# STM32test.net
KiCad netlist of a schematic drawn in Altium Designer
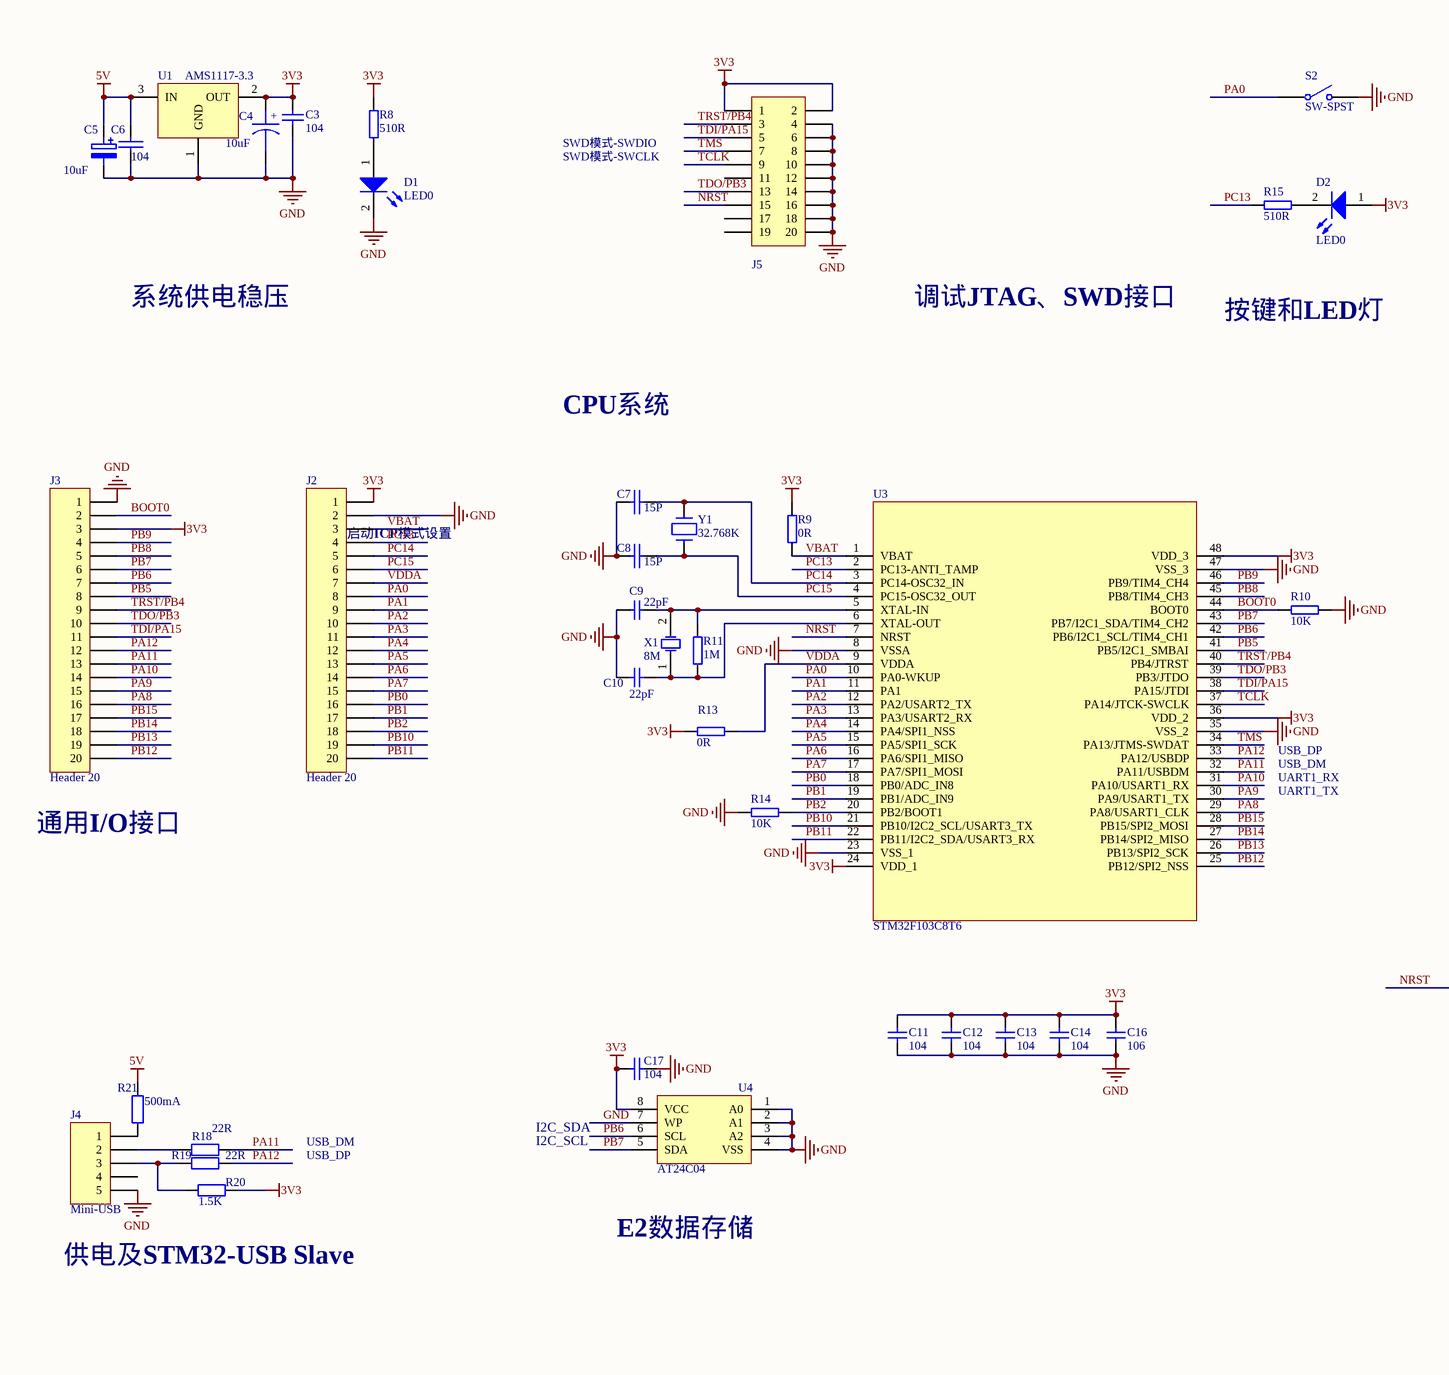
[diagram p0: STM32test.SchDoc, left]
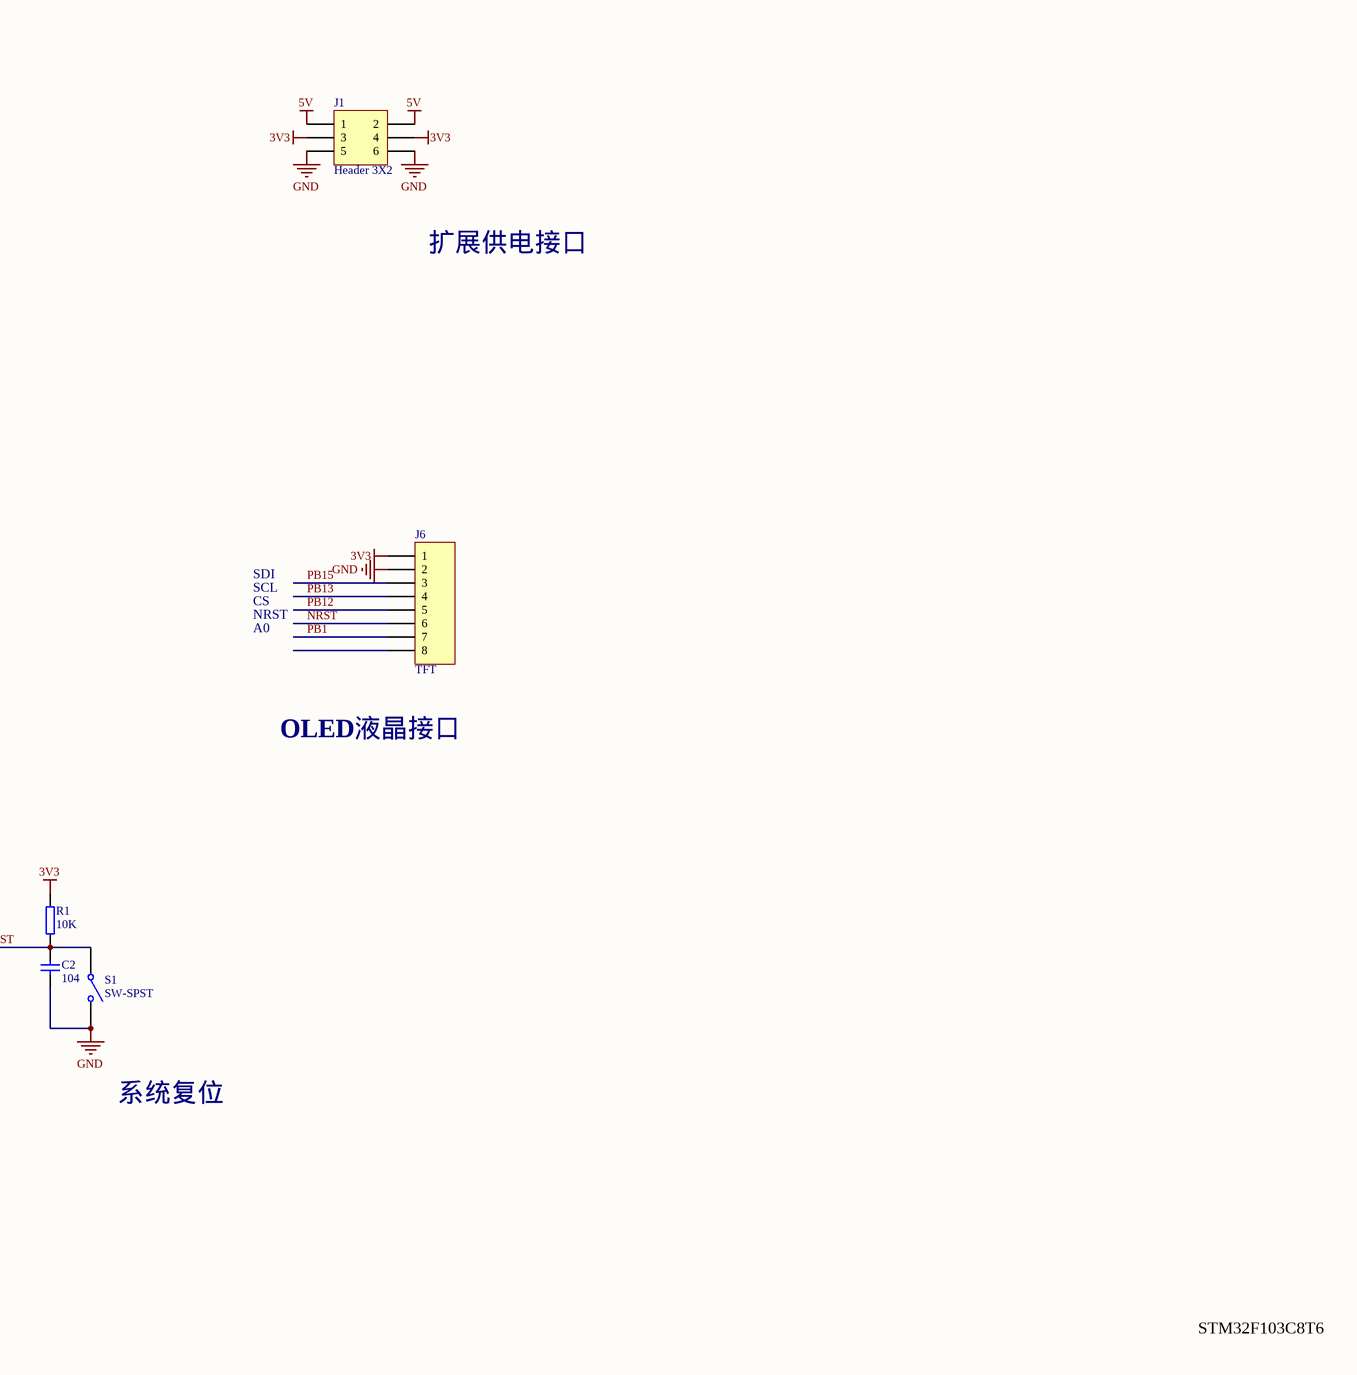
[diagram p1: STM32test.SchDoc, right]

(export (version "E")
  (design (tool "Eeschema 10.0.6"))
  (components
    (comp (ref "C2")
      (value "104")
      (footprint "RC0603")
      (description "Capacitor")
      (fields (field (name "PUBLISHER") "ZL_A0OFFICE"))
      (libsource (lib "CommomDevices") (part "CAP1"))
    )
    (comp (ref "C3")
      (value "104")
      (footprint "RC0603")
      (description "Capacitor")
      (fields (field (name "PUBLISHER") "Altium Limited"))
      (libsource (lib "*") (part "Cap"))
    )
    (comp (ref "C4")
      (value "10uF")
      (footprint "RC0805")
      (description "Capacitor")
      (libsource (lib "*") (part "CAPACITOR POL"))
    )
    (comp (ref "C5") (value "10uF") (footprint "RC0805") (libsource (lib "*") (part "ELECTRO2")))
    (comp (ref "C6")
      (value "104")
      (footprint "RC0603")
      (description "Capacitor")
      (libsource (lib "*") (part "CAP"))
    )
    (comp (ref "C7") (value "15P") (footprint "RC0603") (libsource (lib "") (part "CAP_1")))
    (comp (ref "C8") (value "15P") (footprint "RC0603") (libsource (lib "") (part "CAP_1")))
    (comp (ref "C9")
      (value "22pF")
      (footprint "RC0603")
      (description "Capacitor")
      (fields (field (name "PUBLISHER") "ZL_A0OFFICE"))
      (libsource (lib "CommomDevices") (part "CAP1"))
    )
    (comp (ref "C10")
      (value "22pF")
      (footprint "RC0603")
      (description "Capacitor")
      (fields (field (name "PUBLISHER") "ZL_A0OFFICE"))
      (libsource (lib "CommomDevices") (part "CAP1"))
    )
    (comp (ref "C11")
      (value "104")
      (footprint "RC0603")
      (description "Capacitor")
      (fields (field (name "PUBLISHER") "ZL_A0OFFICE"))
      (libsource (lib "CommomDevices") (part "CAP1"))
    )
    (comp (ref "C12")
      (value "104")
      (footprint "RC0603")
      (description "Capacitor")
      (fields (field (name "PUBLISHER") "ZL_A0OFFICE"))
      (libsource (lib "CommomDevices") (part "CAP1"))
    )
    (comp (ref "C13")
      (value "104")
      (footprint "RC0603")
      (description "Capacitor")
      (fields (field (name "PUBLISHER") "ZL_A0OFFICE"))
      (libsource (lib "CommomDevices") (part "CAP1"))
    )
    (comp (ref "C14")
      (value "104")
      (footprint "RC0603")
      (description "Capacitor")
      (fields (field (name "PUBLISHER") "ZL_A0OFFICE"))
      (libsource (lib "CommomDevices") (part "CAP1"))
    )
    (comp (ref "C16")
      (value "106")
      (footprint "RC0805")
      (description "Capacitor")
      (fields (field (name "PUBLISHER") "ZL_A0OFFICE"))
      (libsource (lib "CommomDevices") (part "CAP1"))
    )
    (comp (ref "C17")
      (value "104")
      (footprint "RC0603")
      (description "Capacitor")
      (libsource (lib "Miscellaneous Devices") (part "Cap"))
    )
    (comp (ref "D1")
      (value "LED0")
      (footprint "LED0805")
      (description "Typical INFRARED GaAs LED")
      (libsource (lib "Miscellaneous Devices") (part "LED0"))
    )
    (comp (ref "D2")
      (value "LED0")
      (footprint "LED0805")
      (description "Typical INFRARED GaAs LED")
      (libsource (lib "Miscellaneous Devices") (part "LED0"))
    )
    (comp (ref "J1")
      (value "Header 3X2")
      (footprint "IDE3X2-2.54")
      (description "Header, 3-Pin, Dual row")
      (fields (field (name "PUBLISHER") "Altium Limited"))
      (libsource (lib "Miscellaneous Connectors") (part "Header 3X2"))
    )
    (comp (ref "J2")
      (value "Header 20")
      (footprint "HDR1X20")
      (description "Header, 20-Pin")
      (fields (field (name "PUBLISHER") "Altium Limited"))
      (libsource (lib "Miscellaneous Connectors") (part "Header 20"))
    )
    (comp (ref "J3")
      (value "Header 20")
      (footprint "HDR1X20")
      (description "Header, 20-Pin")
      (fields (field (name "PUBLISHER") "Altium Limited"))
      (libsource (lib "Miscellaneous Connectors") (part "Header 20"))
    )
    (comp (ref "J4")
      (value "Mini-USB")
      (footprint "mini_USB")
      (description "Header, 5-Pin")
      (libsource (lib "Miscellaneous Connectors") (part "Header 5"))
    )
    (comp (ref "J5")
      (value "~")
      (footprint "JTAG20P")
      (description "Header, 10-Pin, Dual row, Right Angle")
      (fields (field (name "PUBLISHER") "Altium Limited"))
      (libsource (lib "Miscellaneous Connectors") (part "Header 10X2H"))
    )
    (comp (ref "J6")
      (value "TFT")
      (footprint "HDR1X8")
      (description "Header, 8-Pin")
      (libsource (lib "Miscellaneous Connectors") (part "Header 8"))
    )
    (comp (ref "R1") (value "10K") (footprint "RC0603") (libsource (lib "ZIBO V2.0_Main") (part "R")))
    (comp (ref "R8") (value "510R") (footprint "RC0603") (libsource (lib "ZIBO V2.0_Main") (part "R")))
    (comp (ref "R9") (value "0R") (footprint "RC0603") (libsource (lib "ZIBO V2.0_Main") (part "R")))
    (comp (ref "R10") (value "10K") (footprint "RC0603") (libsource (lib "ZIBO V2.0_Main") (part "R")))
    (comp (ref "R11") (value "1M") (footprint "RC0603") (libsource (lib "ZIBO V2.0_Main") (part "R")))
    (comp (ref "R13") (value "0R") (footprint "RC0603") (libsource (lib "ZIBO V2.0_Main") (part "R")))
    (comp (ref "R14") (value "10K") (footprint "RC0603") (libsource (lib "ZIBO V2.0_Main") (part "R")))
    (comp (ref "R15") (value "510R") (footprint "RC0603") (libsource (lib "ZIBO V2.0_Main") (part "R")))
    (comp (ref "R18")
      (value "22R")
      (footprint "RC0603")
      (description "Resistor")
      (libsource (lib "Miscellaneous Devices") (part "Res2"))
    )
    (comp (ref "R19")
      (value "22R")
      (footprint "RC0603")
      (description "Resistor")
      (libsource (lib "Miscellaneous Devices") (part "Res2"))
    )
    (comp (ref "R20")
      (value "1.5K")
      (footprint "RC0603")
      (description "Resistor")
      (libsource (lib "Miscellaneous Devices") (part "Res2"))
    )
    (comp (ref "R21")
      (value "500mA")
      (footprint "RC0805")
      (description "Resistor")
      (libsource (lib "") (part "Res2_1"))
    )
    (comp (ref "S1")
      (value "SW-SPST")
      (footprint "SMT-KEY")
      (description "Single-Pole, Single-Throw Switch")
      (libsource (lib "Miscellaneous Devices") (part "SW-SPST"))
    )
    (comp (ref "S2")
      (value "SW-SPST")
      (footprint "SMT-KEY")
      (description "Single-Pole, Single-Throw Switch")
      (libsource (lib "Miscellaneous Devices") (part "SW-SPST"))
    )
    (comp (ref "U1")
      (value "AMS1117-3.3")
      (footprint "SOT223")
      (libsource (lib "Newcapec9263_Board_NEW") (part "LT1085CM-3.3"))
    )
    (comp (ref "U3")
      (value "STM32F103C8T6")
      (footprint "LQFP48")
      (libsource (lib "STM32_Smart") (part "STM32F103C8T6"))
    )
    (comp (ref "U4") (value "AT24C04") (footprint "SOIC-8P") (libsource (lib "Newcapec9263") (part "EPROM")))
    (comp (ref "X1")
      (value "8M")
      (footprint "SMD49S")
      (description "Crystal Oscillator")
      (fields (field (name "PUBLISHER") "ZL_A0OFFICE"))
      (libsource (lib "CommomDevices") (part "XTAL_SMD"))
    )
    (comp (ref "Y1")
      (value "32.768K")
      (footprint "JZ32768")
      (description "晶振")
      (libsource (lib "*") (part "CRYSTAL"))
    )
  )
  (nets
    (net (code "1") (name "/BOOT0") (class "Default")
      (node (ref "J3") (pin "2") (pinfunction "2_2") (pintype "passive"))
      (node (ref "R10") (pin "2") (pinfunction "2_2") (pintype "passive"))
      (node (ref "U3") (pin "44") (pinfunction "BOOT0_44") (pintype "passive"))
    )
    (net (code "2") (name "/NRST") (class "Default")
      (node (ref "C2") (pin "1") (pinfunction "1_1") (pintype "passive"))
      (node (ref "J5") (pin "15") (pinfunction "15_15") (pintype "passive"))
      (node (ref "J6") (pin "6") (pinfunction "6_6") (pintype "passive"))
      (node (ref "R1") (pin "1") (pinfunction "1_1") (pintype "passive"))
      (node (ref "S1") (pin "1") (pinfunction "COMMON_1") (pintype "passive"))
      (node (ref "U3") (pin "7") (pinfunction "NRST_7") (pintype "passive"))
    )
    (net (code "3") (name "/PA0") (class "Default")
      (node (ref "J2") (pin "8") (pinfunction "8_8") (pintype "passive"))
      (node (ref "S2") (pin "1") (pinfunction "COMMON_1") (pintype "passive"))
      (node (ref "U3") (pin "10") (pinfunction "PA0-WKUP_10") (pintype "passive"))
    )
    (net (code "4") (name "/PA1") (class "Default")
      (node (ref "J2") (pin "9") (pinfunction "9_9") (pintype "passive"))
      (node (ref "U3") (pin "11") (pinfunction "PA1_11") (pintype "passive"))
    )
    (net (code "5") (name "/PA2") (class "Default")
      (node (ref "J2") (pin "10") (pinfunction "10_10") (pintype "passive"))
      (node (ref "U3") (pin "12") (pinfunction "PA2/USART2_TX_12") (pintype "passive"))
    )
    (net (code "6") (name "/PA3") (class "Default")
      (node (ref "J2") (pin "11") (pinfunction "11_11") (pintype "passive"))
      (node (ref "U3") (pin "13") (pinfunction "PA3/USART2_RX_13") (pintype "passive"))
    )
    (net (code "7") (name "/PA4") (class "Default")
      (node (ref "J2") (pin "12") (pinfunction "12_12") (pintype "passive"))
      (node (ref "U3") (pin "14") (pinfunction "PA4/SPI1_NSS_14") (pintype "passive"))
    )
    (net (code "8") (name "/PA5") (class "Default")
      (node (ref "J2") (pin "13") (pinfunction "13_13") (pintype "passive"))
      (node (ref "U3") (pin "15") (pinfunction "PA5/SPI1_SCK_15") (pintype "passive"))
    )
    (net (code "9") (name "/PA6") (class "Default")
      (node (ref "J2") (pin "14") (pinfunction "14_14") (pintype "passive"))
      (node (ref "U3") (pin "16") (pinfunction "PA6/SPI1_MISO_16") (pintype "passive"))
    )
    (net (code "10") (name "/PA7") (class "Default")
      (node (ref "J2") (pin "15") (pinfunction "15_15") (pintype "passive"))
      (node (ref "U3") (pin "17") (pinfunction "PA7/SPI1_MOSI_17") (pintype "passive"))
    )
    (net (code "11") (name "/PA8") (class "Default")
      (node (ref "J3") (pin "16") (pinfunction "16_16") (pintype "passive"))
      (node (ref "U3") (pin "29") (pinfunction "PA8/USART1_CLK_29") (pintype "passive"))
    )
    (net (code "12") (name "/PA9") (class "Default")
      (node (ref "J3") (pin "15") (pinfunction "15_15") (pintype "passive"))
      (node (ref "U3") (pin "30") (pinfunction "PA9/USART1_TX_30") (pintype "passive"))
    )
    (net (code "13") (name "/PA10") (class "Default")
      (node (ref "J3") (pin "14") (pinfunction "14_14") (pintype "passive"))
      (node (ref "U3") (pin "31") (pinfunction "PA10/USART1_RX_31") (pintype "passive"))
    )
    (net (code "14") (name "/PA11") (class "Default")
      (node (ref "J3") (pin "13") (pinfunction "13_13") (pintype "passive"))
      (node (ref "R18") (pin "1") (pinfunction "1_1") (pintype "passive"))
      (node (ref "U3") (pin "32") (pinfunction "PA11/USBDM_32") (pintype "passive"))
    )
    (net (code "15") (name "/PA12") (class "Default")
      (node (ref "J3") (pin "12") (pinfunction "12_12") (pintype "passive"))
      (node (ref "R19") (pin "1") (pinfunction "1_1") (pintype "passive"))
      (node (ref "U3") (pin "33") (pinfunction "PA12/USBDP_33") (pintype "passive"))
    )
    (net (code "16") (name "/PB0") (class "Default")
      (node (ref "J2") (pin "16") (pinfunction "16_16") (pintype "passive"))
      (node (ref "U3") (pin "18") (pinfunction "PB0/ADC_IN8_18") (pintype "passive"))
    )
    (net (code "17") (name "/PB1") (class "Default")
      (node (ref "J2") (pin "17") (pinfunction "17_17") (pintype "passive"))
      (node (ref "J6") (pin "7") (pinfunction "7_7") (pintype "passive"))
      (node (ref "U3") (pin "19") (pinfunction "PB1/ADC_IN9_19") (pintype "passive"))
    )
    (net (code "18") (name "/PB2") (class "Default")
      (node (ref "J2") (pin "18") (pinfunction "18_18") (pintype "passive"))
      (node (ref "R14") (pin "1") (pinfunction "1_1") (pintype "passive"))
      (node (ref "U3") (pin "20") (pinfunction "PB2/BOOT1_20") (pintype "passive"))
    )
    (net (code "19") (name "/PB5") (class "Default")
      (node (ref "J3") (pin "8") (pinfunction "8_8") (pintype "passive"))
      (node (ref "U3") (pin "41") (pinfunction "PB5/I2C1_SMBAI_41") (pintype "passive"))
    )
    (net (code "20") (name "/PB6") (class "Default")
      (node (ref "J3") (pin "7") (pinfunction "7_7") (pintype "passive"))
      (node (ref "U3") (pin "42") (pinfunction "PB6/I2C1_SCL/TIM4_CH1_42") (pintype "passive"))
      (node (ref "U4") (pin "6") (pinfunction "SCL_6") (pintype "passive"))
    )
    (net (code "21") (name "/PB7") (class "Default")
      (node (ref "J3") (pin "6") (pinfunction "6_6") (pintype "passive"))
      (node (ref "U3") (pin "43") (pinfunction "PB7/I2C1_SDA/TIM4_CH2_43") (pintype "passive"))
      (node (ref "U4") (pin "5") (pinfunction "SDA_5") (pintype "passive"))
    )
    (net (code "22") (name "/PB8") (class "Default")
      (node (ref "J3") (pin "5") (pinfunction "5_5") (pintype "passive"))
      (node (ref "U3") (pin "45") (pinfunction "PB8/TIM4_CH3_45") (pintype "passive"))
    )
    (net (code "23") (name "/PB9") (class "Default")
      (node (ref "J3") (pin "4") (pinfunction "4_4") (pintype "passive"))
      (node (ref "U3") (pin "46") (pinfunction "PB9/TIM4_CH4_46") (pintype "passive"))
    )
    (net (code "24") (name "/PB10") (class "Default")
      (node (ref "J2") (pin "19") (pinfunction "19_19") (pintype "passive"))
      (node (ref "U3") (pin "21") (pinfunction "PB10/I2C2_SCL/USART3_TX_21") (pintype "passive"))
    )
    (net (code "25") (name "/PB11") (class "Default")
      (node (ref "J2") (pin "20") (pinfunction "20_20") (pintype "passive"))
      (node (ref "U3") (pin "22") (pinfunction "PB11/I2C2_SDA/USART3_RX_22") (pintype "passive"))
    )
    (net (code "26") (name "/PB12") (class "Default")
      (node (ref "J3") (pin "20") (pinfunction "20_20") (pintype "passive"))
      (node (ref "J6") (pin "5") (pinfunction "5_5") (pintype "passive"))
      (node (ref "U3") (pin "25") (pinfunction "PB12/SPI2_NSS_25") (pintype "passive"))
    )
    (net (code "27") (name "/PB13") (class "Default")
      (node (ref "J3") (pin "19") (pinfunction "19_19") (pintype "passive"))
      (node (ref "J6") (pin "4") (pinfunction "4_4") (pintype "passive"))
      (node (ref "U3") (pin "26") (pinfunction "PB13/SPI2_SCK_26") (pintype "passive"))
    )
    (net (code "28") (name "/PB14") (class "Default")
      (node (ref "J3") (pin "18") (pinfunction "18_18") (pintype "passive"))
      (node (ref "U3") (pin "27") (pinfunction "PB14/SPI2_MISO_27") (pintype "passive"))
    )
    (net (code "29") (name "/PB15") (class "Default")
      (node (ref "J3") (pin "17") (pinfunction "17_17") (pintype "passive"))
      (node (ref "J6") (pin "3") (pinfunction "3_3") (pintype "passive"))
      (node (ref "U3") (pin "28") (pinfunction "PB15/SPI2_MOSI_28") (pintype "passive"))
    )
    (net (code "30") (name "/PC13") (class "Default")
      (node (ref "J2") (pin "4") (pinfunction "4_4") (pintype "passive"))
      (node (ref "R15") (pin "1") (pinfunction "1_1") (pintype "passive"))
      (node (ref "U3") (pin "2") (pinfunction "PC13-ANTI_TAMP_2") (pintype "passive"))
    )
    (net (code "31") (name "/PC14") (class "Default")
      (node (ref "C7") (pin "2") (pintype "passive"))
      (node (ref "J2") (pin "5") (pinfunction "5_5") (pintype "passive"))
      (node (ref "U3") (pin "3") (pinfunction "PC14-OSC32_IN_3") (pintype "passive"))
      (node (ref "Y1") (pin "2") (pintype "passive"))
    )
    (net (code "32") (name "/PC15") (class "Default")
      (node (ref "C8") (pin "2") (pintype "passive"))
      (node (ref "J2") (pin "6") (pinfunction "6_6") (pintype "passive"))
      (node (ref "U3") (pin "4") (pinfunction "PC15-OSC32_OUT_4") (pintype "passive"))
      (node (ref "Y1") (pin "1") (pintype "passive"))
    )
    (net (code "33") (name "/TCLK") (class "Default")
      (node (ref "J5") (pin "9") (pinfunction "9_9") (pintype "passive"))
      (node (ref "U3") (pin "37") (pinfunction "PA14/JTCK-SWCLK_37") (pintype "passive"))
    )
    (net (code "34") (name "/TDI{slash}PA15") (class "Default")
      (node (ref "J3") (pin "11") (pinfunction "11_11") (pintype "passive"))
      (node (ref "J5") (pin "5") (pinfunction "5_5") (pintype "passive"))
      (node (ref "U3") (pin "38") (pinfunction "PA15/JTDI_38") (pintype "passive"))
    )
    (net (code "35") (name "/TDO{slash}PB3") (class "Default")
      (node (ref "J3") (pin "10") (pinfunction "10_10") (pintype "passive"))
      (node (ref "J5") (pin "13") (pinfunction "13_13") (pintype "passive"))
      (node (ref "U3") (pin "39") (pinfunction "PB3/JTDO_39") (pintype "passive"))
    )
    (net (code "36") (name "/TMS") (class "Default")
      (node (ref "J5") (pin "7") (pinfunction "7_7") (pintype "passive"))
      (node (ref "U3") (pin "34") (pinfunction "PA13/JTMS-SWDAT_34") (pintype "passive"))
    )
    (net (code "37") (name "/TRST{slash}PB4") (class "Default")
      (node (ref "J3") (pin "9") (pinfunction "9_9") (pintype "passive"))
      (node (ref "J5") (pin "3") (pinfunction "3_3") (pintype "passive"))
      (node (ref "U3") (pin "40") (pinfunction "PB4/JTRST_40") (pintype "passive"))
    )
    (net (code "38") (name "/VBAT") (class "Default")
      (node (ref "J2") (pin "3") (pinfunction "3_3") (pintype "passive"))
      (node (ref "R9") (pin "1") (pinfunction "1_1") (pintype "passive"))
      (node (ref "U3") (pin "1") (pinfunction "VBAT_1") (pintype "passive"))
    )
    (net (code "39") (name "/VDDA") (class "Default")
      (node (ref "J2") (pin "7") (pinfunction "7_7") (pintype "passive"))
      (node (ref "R13") (pin "1") (pinfunction "1_1") (pintype "passive"))
      (node (ref "U3") (pin "9") (pinfunction "VDDA_9") (pintype "passive"))
    )
    (net (code "40") (name "3V3") (class "Default")
      (node (ref "C11") (pin "1") (pinfunction "1_1") (pintype "passive"))
      (node (ref "C12") (pin "1") (pinfunction "1_1") (pintype "passive"))
      (node (ref "C13") (pin "1") (pinfunction "1_1") (pintype "passive"))
      (node (ref "C14") (pin "1") (pinfunction "1_1") (pintype "passive"))
      (node (ref "C16") (pin "1") (pinfunction "1_1") (pintype "passive"))
      (node (ref "C17") (pin "2") (pinfunction "2_2") (pintype "passive"))
      (node (ref "C3") (pin "1") (pinfunction "1_1") (pintype "passive"))
      (node (ref "C4") (pin "1") (pinfunction "1_1") (pintype "passive"))
      (node (ref "D2") (pin "1") (pinfunction "A_1") (pintype "passive"))
      (node (ref "J1") (pin "3") (pinfunction "3_3") (pintype "passive"))
      (node (ref "J1") (pin "4") (pinfunction "4_4") (pintype "passive"))
      (node (ref "J2") (pin "1") (pinfunction "1_1") (pintype "passive"))
      (node (ref "J3") (pin "3") (pinfunction "3_3") (pintype "passive"))
      (node (ref "J5") (pin "1") (pinfunction "1_1") (pintype "passive"))
      (node (ref "J5") (pin "2") (pinfunction "2_2") (pintype "passive"))
      (node (ref "J6") (pin "1") (pinfunction "1_1") (pintype "passive"))
      (node (ref "R1") (pin "2") (pinfunction "2_2") (pintype "passive"))
      (node (ref "R13") (pin "2") (pinfunction "2_2") (pintype "passive"))
      (node (ref "R20") (pin "1") (pinfunction "1_1") (pintype "passive"))
      (node (ref "R8") (pin "2") (pinfunction "2_2") (pintype "passive"))
      (node (ref "R9") (pin "2") (pinfunction "2_2") (pintype "passive"))
      (node (ref "U1") (pin "2") (pinfunction "OUT_2") (pintype "passive"))
      (node (ref "U3") (pin "24") (pinfunction "VDD_1_24") (pintype "passive"))
      (node (ref "U3") (pin "36") (pinfunction "VDD_2_36") (pintype "passive"))
      (node (ref "U3") (pin "48") (pinfunction "VDD_3_48") (pintype "passive"))
      (node (ref "U4") (pin "8") (pinfunction "VCC_8") (pintype "passive"))
    )
    (net (code "41") (name "5V") (class "Default")
      (node (ref "C5") (pin "1") (pintype "passive"))
      (node (ref "C6") (pin "1") (pinfunction "1_1") (pintype "passive"))
      (node (ref "J1") (pin "1") (pinfunction "1_1") (pintype "passive"))
      (node (ref "J1") (pin "2") (pinfunction "2_2") (pintype "passive"))
      (node (ref "R21") (pin "1") (pinfunction "1_1") (pintype "passive"))
      (node (ref "U1") (pin "3") (pinfunction "IN_3") (pintype "passive"))
    )
    (net (code "42") (name "GND") (class "Default")
      (node (ref "C10") (pin "2") (pinfunction "2_2") (pintype "passive"))
      (node (ref "C11") (pin "2") (pinfunction "2_2") (pintype "passive"))
      (node (ref "C12") (pin "2") (pinfunction "2_2") (pintype "passive"))
      (node (ref "C13") (pin "2") (pinfunction "2_2") (pintype "passive"))
      (node (ref "C14") (pin "2") (pinfunction "2_2") (pintype "passive"))
      (node (ref "C16") (pin "2") (pinfunction "2_2") (pintype "passive"))
      (node (ref "C17") (pin "1") (pinfunction "1_1") (pintype "passive"))
      (node (ref "C2") (pin "2") (pinfunction "2_2") (pintype "passive"))
      (node (ref "C3") (pin "2") (pinfunction "2_2") (pintype "passive"))
      (node (ref "C4") (pin "2") (pinfunction "2_2") (pintype "passive"))
      (node (ref "C5") (pin "2") (pintype "passive"))
      (node (ref "C6") (pin "2") (pinfunction "2_2") (pintype "passive"))
      (node (ref "C7") (pin "1") (pintype "passive"))
      (node (ref "C8") (pin "1") (pintype "passive"))
      (node (ref "C9") (pin "2") (pinfunction "2_2") (pintype "passive"))
      (node (ref "D1") (pin "2") (pinfunction "K_2") (pintype "passive"))
      (node (ref "J1") (pin "5") (pinfunction "5_5") (pintype "passive"))
      (node (ref "J1") (pin "6") (pinfunction "6_6") (pintype "passive"))
      (node (ref "J2") (pin "2") (pinfunction "2_2") (pintype "passive"))
      (node (ref "J3") (pin "1") (pinfunction "1_1") (pintype "passive"))
      (node (ref "J4") (pin "5") (pinfunction "5_5") (pintype "passive"))
      (node (ref "J5") (pin "10") (pinfunction "10_10") (pintype "passive"))
      (node (ref "J5") (pin "12") (pinfunction "12_12") (pintype "passive"))
      (node (ref "J5") (pin "14") (pinfunction "14_14") (pintype "passive"))
      (node (ref "J5") (pin "16") (pinfunction "16_16") (pintype "passive"))
      (node (ref "J5") (pin "18") (pinfunction "18_18") (pintype "passive"))
      (node (ref "J5") (pin "20") (pinfunction "20_20") (pintype "passive"))
      (node (ref "J5") (pin "4") (pinfunction "4_4") (pintype "passive"))
      (node (ref "J5") (pin "6") (pinfunction "6_6") (pintype "passive"))
      (node (ref "J5") (pin "8") (pinfunction "8_8") (pintype "passive"))
      (node (ref "J6") (pin "2") (pinfunction "2_2") (pintype "passive"))
      (node (ref "R10") (pin "1") (pinfunction "1_1") (pintype "passive"))
      (node (ref "R14") (pin "2") (pinfunction "2_2") (pintype "passive"))
      (node (ref "S1") (pin "2") (pinfunction "NO_2") (pintype "passive"))
      (node (ref "S2") (pin "2") (pinfunction "NO_2") (pintype "passive"))
      (node (ref "U1") (pin "1") (pinfunction "GND_1") (pintype "passive"))
      (node (ref "U3") (pin "23") (pinfunction "VSS_1_23") (pintype "passive"))
      (node (ref "U3") (pin "35") (pinfunction "VSS_2_35") (pintype "passive"))
      (node (ref "U3") (pin "47") (pinfunction "VSS_3_47") (pintype "passive"))
      (node (ref "U3") (pin "8") (pinfunction "VSSA_8") (pintype "passive"))
      (node (ref "U4") (pin "1") (pinfunction "A0_1") (pintype "passive"))
      (node (ref "U4") (pin "2") (pinfunction "A1_2") (pintype "passive"))
      (node (ref "U4") (pin "3") (pinfunction "A2_3") (pintype "passive"))
      (node (ref "U4") (pin "4") (pinfunction "VSS_4") (pintype "passive"))
      (node (ref "U4") (pin "7") (pinfunction "WP_7") (pintype "passive"))
    )
    (net (code "43") (name "Net-(D1-A)") (class "Default")
      (node (ref "D1") (pin "1") (pinfunction "A_1") (pintype "passive"))
      (node (ref "R8") (pin "1") (pinfunction "1_1") (pintype "passive"))
    )
    (net (code "44") (name "Net-(D2-K)") (class "Default")
      (node (ref "D2") (pin "2") (pinfunction "K_2") (pintype "passive"))
      (node (ref "R15") (pin "2") (pinfunction "2_2") (pintype "passive"))
    )
    (net (code "45") (name "Net-(J4-Pad1)") (class "Default")
      (node (ref "J4") (pin "1") (pinfunction "1_1") (pintype "passive"))
      (node (ref "R21") (pin "2") (pinfunction "2_2") (pintype "passive"))
    )
    (net (code "46") (name "Net-(J4-Pad2)") (class "Default")
      (node (ref "J4") (pin "2") (pinfunction "2_2") (pintype "passive"))
      (node (ref "R18") (pin "2") (pinfunction "2_2") (pintype "passive"))
    )
    (net (code "47") (name "Net-(J4-Pad3)") (class "Default")
      (node (ref "J4") (pin "3") (pinfunction "3_3") (pintype "passive"))
      (node (ref "R19") (pin "2") (pinfunction "2_2") (pintype "passive"))
      (node (ref "R20") (pin "2") (pinfunction "2_2") (pintype "passive"))
    )
    (net (code "48") (name "Net-(U3-XTAL-IN)") (class "Default")
      (node (ref "C9") (pin "1") (pinfunction "1_1") (pintype "passive"))
      (node (ref "R11") (pin "2") (pinfunction "2_2") (pintype "passive"))
      (node (ref "U3") (pin "5") (pinfunction "XTAL-IN_5") (pintype "passive"))
      (node (ref "X1") (pin "2") (pinfunction "2_2") (pintype "passive"))
    )
    (net (code "49") (name "Net-(U3-XTAL-OUT)") (class "Default")
      (node (ref "C10") (pin "1") (pinfunction "1_1") (pintype "passive"))
      (node (ref "R11") (pin "1") (pinfunction "1_1") (pintype "passive"))
      (node (ref "U3") (pin "6") (pinfunction "XTAL-OUT_6") (pintype "passive"))
      (node (ref "X1") (pin "1") (pinfunction "1_1") (pintype "passive"))
    )
    (net (code "50") (name "unconnected-(J4-Pad4)") (class "Default")
      (node (ref "J4") (pin "4") (pinfunction "4_4") (pintype "passive"))
    )
    (net (code "51") (name "unconnected-(J5-Pad11)") (class "Default")
      (node (ref "J5") (pin "11") (pinfunction "11_11") (pintype "passive"))
    )
    (net (code "52") (name "unconnected-(J5-Pad17)") (class "Default")
      (node (ref "J5") (pin "17") (pinfunction "17_17") (pintype "passive"))
    )
    (net (code "53") (name "unconnected-(J5-Pad19)") (class "Default")
      (node (ref "J5") (pin "19") (pinfunction "19_19") (pintype "passive"))
    )
    (net (code "54") (name "unconnected-(J6-Pad8)") (class "Default")
      (node (ref "J6") (pin "8") (pinfunction "8_8") (pintype "passive"))
    )
  )
)
